# SonicScrewdriverThru.net
KiCad netlist of a schematic drawn in EAGLE
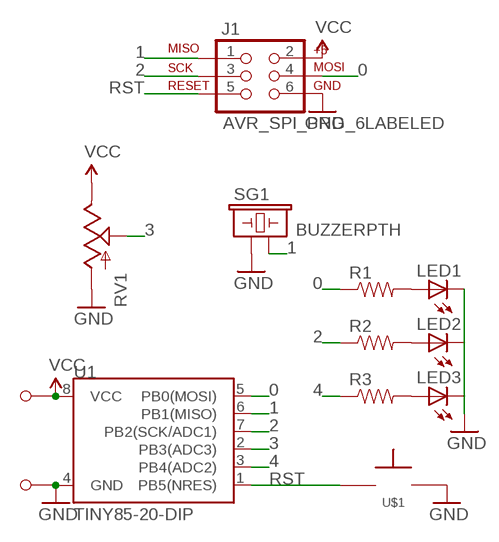
[diagram p0: schematic, sheet 1]

(export (version "E")
  (design (tool "Eeschema 10.0.6"))
  (components
    (comp (ref "J1")
      (value "AVR_SPI_PRG_6LABELED")
      (footprint "eagle-import:2X3-NS")
      (libsource (lib "eagle-import") (part "AVR_SPI_PRG_6LABELED"))
    )
    (comp (ref "LED1")
      (value "LEDOVAL")
      (footprint "eagle-import:LED-OVAL")
      (libsource (lib "eagle-import") (part "LEDOVAL"))
    )
    (comp (ref "LED2")
      (value "LEDOVAL")
      (footprint "eagle-import:LED-OVAL")
      (libsource (lib "eagle-import") (part "LEDOVAL"))
    )
    (comp (ref "LED3")
      (value "LEDOVAL")
      (footprint "eagle-import:LED-OVAL")
      (libsource (lib "eagle-import") (part "LEDOVAL"))
    )
    (comp (ref "R1")
      (value "RESISTORAXIAL-0.3")
      (footprint "eagle-import:AXIAL-0.3")
      (libsource (lib "eagle-import") (part "RESISTORAXIAL-0.3"))
    )
    (comp (ref "R2")
      (value "RESISTORAXIAL-0.3")
      (footprint "eagle-import:AXIAL-0.3")
      (libsource (lib "eagle-import") (part "RESISTORAXIAL-0.3"))
    )
    (comp (ref "R3")
      (value "RESISTORAXIAL-0.3")
      (footprint "eagle-import:AXIAL-0.3")
      (libsource (lib "eagle-import") (part "RESISTORAXIAL-0.3"))
    )
    (comp (ref "RV1")
      (value "POTTHUMB")
      (footprint "eagle-import:THUMB")
      (libsource (lib "eagle-import") (part "POTTHUMB"))
    )
    (comp (ref "SG1")
      (value "BUZZERPTH")
      (footprint "eagle-import:BUZZER-12MM")
      (libsource (lib "eagle-import") (part "BUZZERPTH"))
    )
    (comp (ref "U$1")
      (value "TAC_SPST_NO")
      (footprint "eagle-import:TAC_SPST_NO")
      (libsource (lib "eagle-import") (part "TAC_SPST_NO"))
    )
    (comp (ref "U$2")
      (value "M1")
      (footprint "eagle-import:M1_NO_STRAIN")
      (libsource (lib "eagle-import") (part "M1"))
    )
    (comp (ref "U$3")
      (value "M1")
      (footprint "eagle-import:M1_NO_STRAIN")
      (libsource (lib "eagle-import") (part "M1"))
    )
    (comp (ref "U1")
      (value "TINY85-20-DIP")
      (footprint "eagle-import:DIP08")
      (libsource (lib "eagle-import") (part "ATTINY45TINY85-20-DIP"))
    )
  )
  (nets
    (net (code "1") (name "/0") (class "Default")
      (node (ref "J1") (pin "4") (pinfunction "4_4") (pintype "passive"))
      (node (ref "R1") (pin "P$1") (pinfunction "1_P$1") (pintype "passive"))
      (node (ref "U1") (pin "5") (pinfunction "PB0(MOSI)_5") (pintype "bidirectional"))
    )
    (net (code "2") (name "/1") (class "Default")
      (node (ref "J1") (pin "1") (pinfunction "1_1") (pintype "passive"))
      (node (ref "SG1") (pin "-") (pinfunction "2_-") (pintype "passive"))
      (node (ref "U1") (pin "6") (pinfunction "PB1(MISO)_6") (pintype "bidirectional"))
    )
    (net (code "3") (name "/2") (class "Default")
      (node (ref "J1") (pin "3") (pinfunction "3_3") (pintype "passive"))
      (node (ref "R2") (pin "P$1") (pinfunction "1_P$1") (pintype "passive"))
      (node (ref "U1") (pin "7") (pinfunction "PB2(SCK/ADC1)_7") (pintype "bidirectional"))
    )
    (net (code "4") (name "/3") (class "Default")
      (node (ref "RV1") (pin "B") (pinfunction "S_B") (pintype "passive"))
      (node (ref "U1") (pin "2") (pinfunction "PB3(ADC3)_2") (pintype "bidirectional"))
    )
    (net (code "5") (name "/4") (class "Default")
      (node (ref "R3") (pin "P$1") (pinfunction "1_P$1") (pintype "passive"))
      (node (ref "U1") (pin "3") (pinfunction "PB4(ADC2)_3") (pintype "bidirectional"))
    )
    (net (code "6") (name "/RST") (class "Default")
      (node (ref "J1") (pin "5") (pinfunction "5_5") (pintype "passive"))
      (node (ref "U$1") (pin "P$1") (pinfunction "P$1_P$1") (pintype "bidirectional"))
      (node (ref "U1") (pin "1") (pinfunction "PB5(NRES)_1") (pintype "bidirectional"))
    )
    (net (code "7") (name "GND") (class "Default")
      (node (ref "J1") (pin "6") (pinfunction "6_6") (pintype "passive"))
      (node (ref "LED1") (pin "CATHODE") (pinfunction "C_CATHODE") (pintype "passive"))
      (node (ref "LED2") (pin "CATHODE") (pinfunction "C_CATHODE") (pintype "passive"))
      (node (ref "LED3") (pin "CATHODE") (pinfunction "C_CATHODE") (pintype "passive"))
      (node (ref "RV1") (pin "A") (pinfunction "A_A") (pintype "passive"))
      (node (ref "SG1") (pin "+") (pinfunction "1_+") (pintype "passive"))
      (node (ref "U$1") (pin "P$2") (pinfunction "P$2_P$2") (pintype "bidirectional"))
      (node (ref "U$3") (pin "P$1") (pinfunction "P$1_P$1") (pintype "bidirectional"))
      (node (ref "U1") (pin "4") (pinfunction "GND_4") (pintype "bidirectional"))
    )
    (net (code "8") (name "Net-(LED1-A)") (class "Default")
      (node (ref "LED1") (pin "ANODE") (pinfunction "A_ANODE") (pintype "passive"))
      (node (ref "R1") (pin "P$2") (pinfunction "2_P$2") (pintype "passive"))
    )
    (net (code "9") (name "Net-(LED2-A)") (class "Default")
      (node (ref "LED2") (pin "ANODE") (pinfunction "A_ANODE") (pintype "passive"))
      (node (ref "R2") (pin "P$2") (pinfunction "2_P$2") (pintype "passive"))
    )
    (net (code "10") (name "Net-(LED3-A)") (class "Default")
      (node (ref "LED3") (pin "ANODE") (pinfunction "A_ANODE") (pintype "passive"))
      (node (ref "R3") (pin "P$2") (pinfunction "2_P$2") (pintype "passive"))
    )
    (net (code "11") (name "VCC") (class "Default")
      (node (ref "J1") (pin "2") (pinfunction "2_2") (pintype "passive"))
      (node (ref "RV1") (pin "C") (pinfunction "E_C") (pintype "passive"))
      (node (ref "U$2") (pin "P$1") (pinfunction "P$1_P$1") (pintype "bidirectional"))
      (node (ref "U1") (pin "8") (pinfunction "VCC_8") (pintype "bidirectional"))
    )
  )
)
